# Scholar_Robotic_SCH.net
KiCad netlist of a schematic drawn in Altium Designer
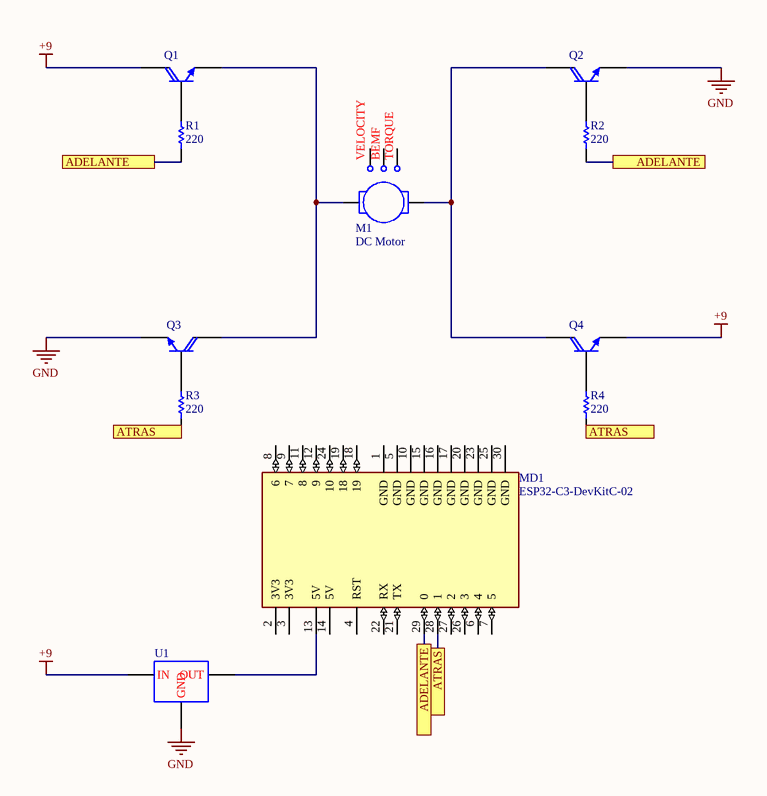
[diagram p0: Scholar Robotic SCH.SchDoc]

(export (version "E")
  (design (tool "Eeschema 10.0.6"))
  (components
    (comp (ref "M1") (value "DC Motor") (libsource (lib "Simulation Generic Components") (part "DC Motor")))
    (comp (ref "MD1")
      (value "ESP32-C3-DevKitC-02")
      (footprint "FP-ESP32-C3-DevKitC-02-MFG")
      (description "ESP32-C3-WROOM-02 DEV BRD")
      (libsource (lib "Scholar Robotic SCH LIB") (part "CMP-194061-000001-1"))
    )
    (comp (ref "Q1")
      (value "Darlington NPN Bipolar Transistor")
      (libsource (lib "Simulation Generic Components") (part "Darlington BJT NPN"))
    )
    (comp (ref "Q2")
      (value "Darlington NPN Bipolar Transistor")
      (libsource (lib "Simulation Generic Components") (part "Darlington BJT NPN"))
    )
    (comp (ref "Q3")
      (value "Darlington NPN Bipolar Transistor")
      (libsource (lib "Simulation Generic Components") (part "Darlington BJT NPN"))
    )
    (comp (ref "Q4")
      (value "Darlington NPN Bipolar Transistor")
      (libsource (lib "Simulation Generic Components") (part "Darlington BJT NPN"))
    )
    (comp (ref "R1")
      (value "220")
      (description "Resistor")
      (libsource (lib "Simulation Generic Components") (part "Resistor"))
    )
    (comp (ref "R2")
      (value "220")
      (description "Resistor")
      (libsource (lib "Simulation Generic Components") (part "Resistor"))
    )
    (comp (ref "R3")
      (value "220")
      (description "Resistor")
      (libsource (lib "Simulation Generic Components") (part "Resistor"))
    )
    (comp (ref "R4")
      (value "220")
      (description "Resistor")
      (libsource (lib "Simulation Generic Components") (part "Resistor"))
    )
    (comp (ref "U1")
      (value "Positive Fixed Voltage regulator")
      (libsource (lib "Simulation Generic Components") (part "Linear Voltage Regulator (Fixed)"))
    )
  )
  (nets
    (net (code "1") (name "+9") (class "Default")
      (node (ref "Q1") (pin "1") (pinfunction "C_1") (pintype "passive"))
      (node (ref "Q4") (pin "3") (pinfunction "E_3") (pintype "passive"))
      (node (ref "U1") (pin "1") (pinfunction "IN_1") (pintype "passive"))
    )
    (net (code "2") (name "/ADELANTE") (class "Default")
      (node (ref "MD1") (pin "29") (pinfunction "0_29") (pintype "bidirectional"))
      (node (ref "R1") (pin "1") (pinfunction "1_1") (pintype "passive"))
      (node (ref "R2") (pin "1") (pinfunction "1_1") (pintype "passive"))
    )
    (net (code "3") (name "/ATRAS") (class "Default")
      (node (ref "MD1") (pin "28") (pinfunction "1_28") (pintype "bidirectional"))
      (node (ref "R3") (pin "1") (pinfunction "1_1") (pintype "passive"))
      (node (ref "R4") (pin "1") (pinfunction "1_1") (pintype "passive"))
    )
    (net (code "4") (name "GND") (class "Default")
      (node (ref "Q2") (pin "3") (pinfunction "E_3") (pintype "passive"))
      (node (ref "Q3") (pin "3") (pinfunction "E_3") (pintype "passive"))
      (node (ref "U1") (pin "2") (pinfunction "GND_2") (pintype "passive"))
    )
    (net (code "5") (name "Net-(Q1-B)") (class "Default")
      (node (ref "Q1") (pin "2") (pinfunction "B_2") (pintype "passive"))
      (node (ref "R1") (pin "2") (pinfunction "2_2") (pintype "passive"))
    )
    (net (code "6") (name "Net-(Q1-E)") (class "Default")
      (node (ref "M1") (pin "1") (pinfunction "1_1") (pintype "passive"))
      (node (ref "Q1") (pin "3") (pinfunction "E_3") (pintype "passive"))
      (node (ref "Q3") (pin "1") (pinfunction "C_1") (pintype "passive"))
    )
    (net (code "7") (name "Net-(Q2-B)") (class "Default")
      (node (ref "Q2") (pin "2") (pinfunction "B_2") (pintype "passive"))
      (node (ref "R2") (pin "2") (pinfunction "2_2") (pintype "passive"))
    )
    (net (code "8") (name "Net-(Q2-C)") (class "Default")
      (node (ref "M1") (pin "2") (pinfunction "2_2") (pintype "passive"))
      (node (ref "Q2") (pin "1") (pinfunction "C_1") (pintype "passive"))
      (node (ref "Q4") (pin "1") (pinfunction "C_1") (pintype "passive"))
    )
    (net (code "9") (name "Net-(Q3-B)") (class "Default")
      (node (ref "Q3") (pin "2") (pinfunction "B_2") (pintype "passive"))
      (node (ref "R3") (pin "2") (pinfunction "2_2") (pintype "passive"))
    )
    (net (code "10") (name "Net-(Q4-B)") (class "Default")
      (node (ref "Q4") (pin "2") (pinfunction "B_2") (pintype "passive"))
      (node (ref "R4") (pin "2") (pinfunction "2_2") (pintype "passive"))
    )
    (net (code "11") (name "Net-(U1-OUT)") (class "Default")
      (node (ref "MD1") (pin "13") (pinfunction "5V_13") (pintype "power_in"))
      (node (ref "U1") (pin "3") (pinfunction "OUT_3") (pintype "passive"))
    )
    (net (code "12") (name "unconnected-(M1-Pad3)") (class "Default")
      (node (ref "M1") (pin "3") (pinfunction "3_3") (pintype "passive"))
    )
    (net (code "13") (name "unconnected-(M1-Pad4)") (class "Default")
      (node (ref "M1") (pin "4") (pinfunction "4_4") (pintype "passive"))
    )
    (net (code "14") (name "unconnected-(M1-Pad5)") (class "Default")
      (node (ref "M1") (pin "5") (pinfunction "5_5") (pintype "passive"))
    )
    (net (code "15") (name "unconnected-(MD1-2-Pad27)") (class "Default")
      (node (ref "MD1") (pin "27") (pinfunction "2_27") (pintype "bidirectional"))
    )
    (net (code "16") (name "unconnected-(MD1-3-Pad26)") (class "Default")
      (node (ref "MD1") (pin "26") (pinfunction "3_26") (pintype "bidirectional"))
    )
    (net (code "17") (name "unconnected-(MD1-3V3-Pad2)") (class "Default")
      (node (ref "MD1") (pin "2") (pinfunction "3V3_2") (pintype "power_in"))
    )
    (net (code "18") (name "unconnected-(MD1-3V3-Pad3)") (class "Default")
      (node (ref "MD1") (pin "3") (pinfunction "3V3_3") (pintype "power_in"))
    )
    (net (code "19") (name "unconnected-(MD1-4-Pad6)") (class "Default")
      (node (ref "MD1") (pin "6") (pinfunction "4_6") (pintype "bidirectional"))
    )
    (net (code "20") (name "unconnected-(MD1-5-Pad7)") (class "Default")
      (node (ref "MD1") (pin "7") (pinfunction "5_7") (pintype "bidirectional"))
    )
    (net (code "21") (name "unconnected-(MD1-5V-Pad14)") (class "Default")
      (node (ref "MD1") (pin "14") (pinfunction "5V_14") (pintype "power_in"))
    )
    (net (code "22") (name "unconnected-(MD1-6-Pad8)") (class "Default")
      (node (ref "MD1") (pin "8") (pinfunction "6_8") (pintype "bidirectional"))
    )
    (net (code "23") (name "unconnected-(MD1-7-Pad9)") (class "Default")
      (node (ref "MD1") (pin "9") (pinfunction "7_9") (pintype "bidirectional"))
    )
    (net (code "24") (name "unconnected-(MD1-8-Pad11)") (class "Default")
      (node (ref "MD1") (pin "11") (pinfunction "8_11") (pintype "bidirectional"))
    )
    (net (code "25") (name "unconnected-(MD1-9-Pad12)") (class "Default")
      (node (ref "MD1") (pin "12") (pinfunction "9_12") (pintype "bidirectional"))
    )
    (net (code "26") (name "unconnected-(MD1-10-Pad24)") (class "Default")
      (node (ref "MD1") (pin "24") (pinfunction "10_24") (pintype "bidirectional"))
    )
    (net (code "27") (name "unconnected-(MD1-18-Pad19)") (class "Default")
      (node (ref "MD1") (pin "19") (pinfunction "18_19") (pintype "bidirectional"))
    )
    (net (code "28") (name "unconnected-(MD1-19-Pad18)") (class "Default")
      (node (ref "MD1") (pin "18") (pinfunction "19_18") (pintype "bidirectional"))
    )
    (net (code "29") (name "unconnected-(MD1-GND-Pad1)") (class "Default")
      (node (ref "MD1") (pin "1") (pinfunction "GND_1") (pintype "power_in"))
    )
    (net (code "30") (name "unconnected-(MD1-GND-Pad5)") (class "Default")
      (node (ref "MD1") (pin "5") (pinfunction "GND_5") (pintype "power_in"))
    )
    (net (code "31") (name "unconnected-(MD1-GND-Pad10)") (class "Default")
      (node (ref "MD1") (pin "10") (pinfunction "GND_10") (pintype "power_in"))
    )
    (net (code "32") (name "unconnected-(MD1-GND-Pad15)") (class "Default")
      (node (ref "MD1") (pin "15") (pinfunction "GND_15") (pintype "power_in"))
    )
    (net (code "33") (name "unconnected-(MD1-GND-Pad16)") (class "Default")
      (node (ref "MD1") (pin "16") (pinfunction "GND_16") (pintype "power_in"))
    )
    (net (code "34") (name "unconnected-(MD1-GND-Pad17)") (class "Default")
      (node (ref "MD1") (pin "17") (pinfunction "GND_17") (pintype "power_in"))
    )
    (net (code "35") (name "unconnected-(MD1-GND-Pad20)") (class "Default")
      (node (ref "MD1") (pin "20") (pinfunction "GND_20") (pintype "power_in"))
    )
    (net (code "36") (name "unconnected-(MD1-GND-Pad23)") (class "Default")
      (node (ref "MD1") (pin "23") (pinfunction "GND_23") (pintype "power_in"))
    )
    (net (code "37") (name "unconnected-(MD1-GND-Pad25)") (class "Default")
      (node (ref "MD1") (pin "25") (pinfunction "GND_25") (pintype "power_in"))
    )
    (net (code "38") (name "unconnected-(MD1-GND-Pad30)") (class "Default")
      (node (ref "MD1") (pin "30") (pinfunction "GND_30") (pintype "power_in"))
    )
    (net (code "39") (name "unconnected-(MD1-RST-Pad4)") (class "Default")
      (node (ref "MD1") (pin "4") (pinfunction "RST_4") (pintype "passive"))
    )
    (net (code "40") (name "unconnected-(MD1-RX-Pad22)") (class "Default")
      (node (ref "MD1") (pin "22") (pinfunction "RX_22") (pintype "bidirectional"))
    )
    (net (code "41") (name "unconnected-(MD1-TX-Pad21)") (class "Default")
      (node (ref "MD1") (pin "21") (pinfunction "TX_21") (pintype "bidirectional"))
    )
  )
)
